# fpga-bank3-inside.net
KiCad netlist of a schematic drawn in Altium Designer
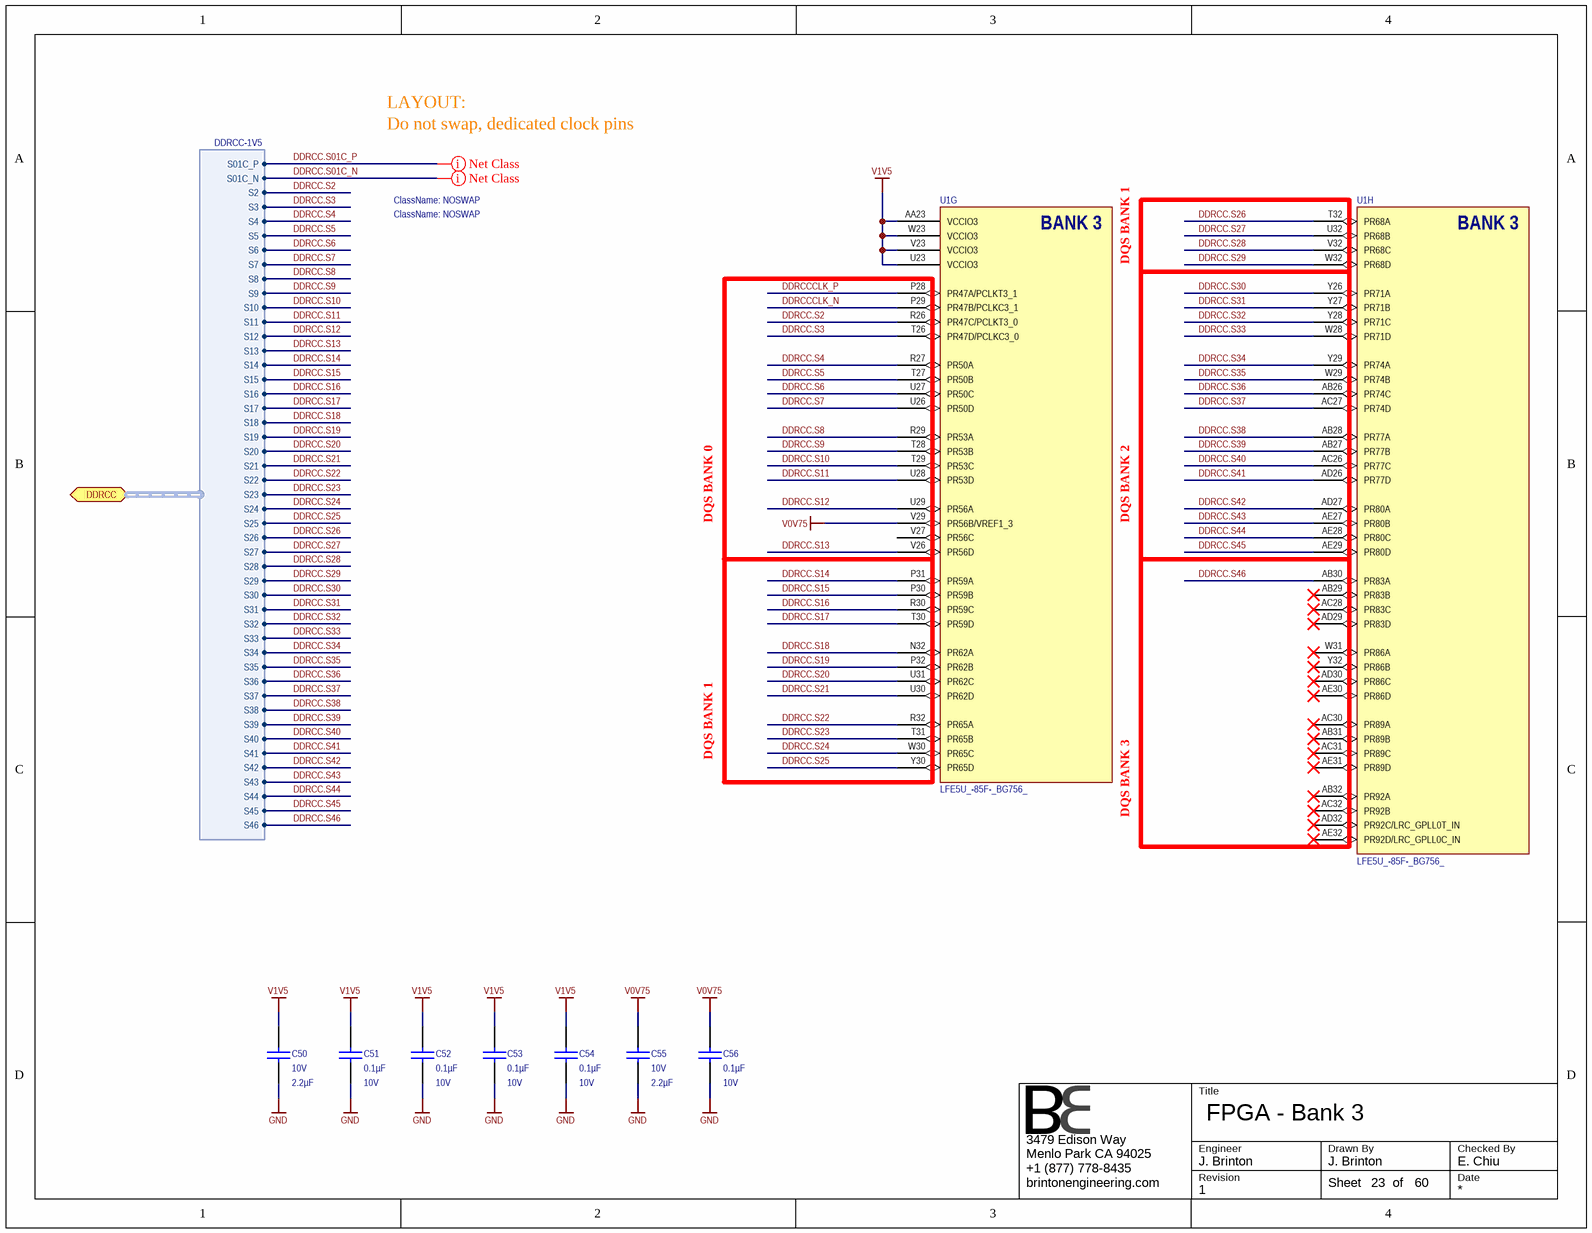
[diagram p0: fpga-bank3-inside.SchDoc]

(export (version "E")
  (design (tool "Eeschema 10.0.6"))
  (components
    (comp (ref "C50")
      (value "GRM188R71A225KE15D")
      (footprint "CAPC1608X90N")
      (description "CAP CER 2.2UF 10V 10% X7R 0603")
      (fields
        (field (name "MANUFACTURER") "Murata Electronics North America")
        (field (name "TOLERANCE") "±10%")
        (field (name "VOLTAGE - RATED") "10V")
        (field (name "CAPACITANCE") "2.2µF")
      )
      (libsource (lib "murata") (part "GRM188R71A225KE15D"))
    )
    (comp (ref "C51")
      (value "GRM155R71A104KA01J")
      (footprint "CAPC1005X56N")
      (description "CAP CER 0.1UF 10V 10% X7R 0402")
      (fields
        (field (name "MANUFACTURER") "Murata Electronics North America")
        (field (name "TOLERANCE") "±10%")
        (field (name "CAPACITANCE") "0.1µF")
        (field (name "VOLTAGE - RATED") "10V")
      )
      (libsource (lib "murata") (part "GRM155R71A104KA01J"))
    )
    (comp (ref "C52")
      (value "GRM155R71A104KA01J")
      (footprint "CAPC1005X56N")
      (description "CAP CER 0.1UF 10V 10% X7R 0402")
      (fields
        (field (name "MANUFACTURER") "Murata Electronics North America")
        (field (name "TOLERANCE") "±10%")
        (field (name "CAPACITANCE") "0.1µF")
        (field (name "VOLTAGE - RATED") "10V")
      )
      (libsource (lib "murata") (part "GRM155R71A104KA01J"))
    )
    (comp (ref "C53")
      (value "GRM155R71A104KA01J")
      (footprint "CAPC1005X56N")
      (description "CAP CER 0.1UF 10V 10% X7R 0402")
      (fields
        (field (name "MANUFACTURER") "Murata Electronics North America")
        (field (name "TOLERANCE") "±10%")
        (field (name "CAPACITANCE") "0.1µF")
        (field (name "VOLTAGE - RATED") "10V")
      )
      (libsource (lib "murata") (part "GRM155R71A104KA01J"))
    )
    (comp (ref "C54")
      (value "GRM155R71A104KA01J")
      (footprint "CAPC1005X56N")
      (description "CAP CER 0.1UF 10V 10% X7R 0402")
      (fields
        (field (name "MANUFACTURER") "Murata Electronics North America")
        (field (name "TOLERANCE") "±10%")
        (field (name "CAPACITANCE") "0.1µF")
        (field (name "VOLTAGE - RATED") "10V")
      )
      (libsource (lib "murata") (part "GRM155R71A104KA01J"))
    )
    (comp (ref "C55")
      (value "GRM188R71A225KE15D")
      (footprint "CAPC1608X90N")
      (description "CAP CER 2.2UF 10V 10% X7R 0603")
      (fields
        (field (name "MANUFACTURER") "Murata Electronics North America")
        (field (name "TOLERANCE") "±10%")
        (field (name "VOLTAGE - RATED") "10V")
        (field (name "CAPACITANCE") "2.2µF")
      )
      (libsource (lib "murata") (part "GRM188R71A225KE15D"))
    )
    (comp (ref "C56")
      (value "GRM155R71A104KA01J")
      (footprint "CAPC1005X56N")
      (description "CAP CER 0.1UF 10V 10% X7R 0402")
      (fields
        (field (name "MANUFACTURER") "Murata Electronics North America")
        (field (name "TOLERANCE") "±10%")
        (field (name "CAPACITANCE") "0.1µF")
        (field (name "VOLTAGE - RATED") "10V")
      )
      (libsource (lib "murata") (part "GRM155R71A104KA01J"))
    )
    (comp (ref "U1")
      (value "LFE5U_-85F-_BG756_")
      (footprint "lattice:caBGA756")
      (description "ECP5 FPGA, 85k LUT, 756-caBGA")
      (fields (field (name "MANUFACTURER") "Lattice Semiconductor"))
      (libsource (lib "lattice") (part "LFE5U_-85F-_BG756_"))
    )
  )
  (nets
    (net (code "4") (name "/DDRCC.S2") (class "Default")
      (node (ref "U1") (pin "R26") (pinfunction "PR47C/PCLKT3_0_R26") (pintype "bidirectional"))
    )
    (net (code "5") (name "/DDRCC.S3") (class "Default")
      (node (ref "U1") (pin "T26") (pinfunction "PR47D/PCLKC3_0_T26") (pintype "bidirectional"))
    )
    (net (code "6") (name "/DDRCC.S4") (class "Default")
      (node (ref "U1") (pin "R27") (pinfunction "PR50A_R27") (pintype "bidirectional"))
    )
    (net (code "7") (name "/DDRCC.S5") (class "Default")
      (node (ref "U1") (pin "T27") (pinfunction "PR50B_T27") (pintype "bidirectional"))
    )
    (net (code "8") (name "/DDRCC.S6") (class "Default")
      (node (ref "U1") (pin "U27") (pinfunction "PR50C_U27") (pintype "bidirectional"))
    )
    (net (code "9") (name "/DDRCC.S7") (class "Default")
      (node (ref "U1") (pin "U26") (pinfunction "PR50D_U26") (pintype "bidirectional"))
    )
    (net (code "10") (name "/DDRCC.S8") (class "Default")
      (node (ref "U1") (pin "R29") (pinfunction "PR53A_R29") (pintype "bidirectional"))
    )
    (net (code "11") (name "/DDRCC.S9") (class "Default")
      (node (ref "U1") (pin "T28") (pinfunction "PR53B_T28") (pintype "bidirectional"))
    )
    (net (code "12") (name "/DDRCC.S10") (class "Default")
      (node (ref "U1") (pin "T29") (pinfunction "PR53C_T29") (pintype "bidirectional"))
    )
    (net (code "13") (name "/DDRCC.S11") (class "Default")
      (node (ref "U1") (pin "U28") (pinfunction "PR53D_U28") (pintype "bidirectional"))
    )
    (net (code "14") (name "/DDRCC.S12") (class "Default")
      (node (ref "U1") (pin "U29") (pinfunction "PR56A_U29") (pintype "bidirectional"))
    )
    (net (code "15") (name "/DDRCC.S13") (class "Default")
      (node (ref "U1") (pin "V26") (pinfunction "PR56D_V26") (pintype "bidirectional"))
    )
    (net (code "16") (name "/DDRCC.S14") (class "Default")
      (node (ref "U1") (pin "P31") (pinfunction "PR59A_P31") (pintype "bidirectional"))
    )
    (net (code "17") (name "/DDRCC.S15") (class "Default")
      (node (ref "U1") (pin "P30") (pinfunction "PR59B_P30") (pintype "bidirectional"))
    )
    (net (code "18") (name "/DDRCC.S16") (class "Default")
      (node (ref "U1") (pin "R30") (pinfunction "PR59C_R30") (pintype "bidirectional"))
    )
    (net (code "19") (name "/DDRCC.S17") (class "Default")
      (node (ref "U1") (pin "T30") (pinfunction "PR59D_T30") (pintype "bidirectional"))
    )
    (net (code "20") (name "/DDRCC.S18") (class "Default")
      (node (ref "U1") (pin "N32") (pinfunction "PR62A_N32") (pintype "bidirectional"))
    )
    (net (code "21") (name "/DDRCC.S19") (class "Default")
      (node (ref "U1") (pin "P32") (pinfunction "PR62B_P32") (pintype "bidirectional"))
    )
    (net (code "22") (name "/DDRCC.S20") (class "Default")
      (node (ref "U1") (pin "U31") (pinfunction "PR62C_U31") (pintype "bidirectional"))
    )
    (net (code "23") (name "/DDRCC.S21") (class "Default")
      (node (ref "U1") (pin "U30") (pinfunction "PR62D_U30") (pintype "bidirectional"))
    )
    (net (code "24") (name "/DDRCC.S22") (class "Default")
      (node (ref "U1") (pin "R32") (pinfunction "PR65A_R32") (pintype "bidirectional"))
    )
    (net (code "25") (name "/DDRCC.S23") (class "Default")
      (node (ref "U1") (pin "T31") (pinfunction "PR65B_T31") (pintype "bidirectional"))
    )
    (net (code "26") (name "/DDRCC.S24") (class "Default")
      (node (ref "U1") (pin "W30") (pinfunction "PR65C_W30") (pintype "bidirectional"))
    )
    (net (code "27") (name "/DDRCC.S25") (class "Default")
      (node (ref "U1") (pin "Y30") (pinfunction "PR65D_Y30") (pintype "bidirectional"))
    )
    (net (code "28") (name "/DDRCC.S26") (class "Default")
      (node (ref "U1") (pin "T32") (pinfunction "PR68A_T32") (pintype "bidirectional"))
    )
    (net (code "29") (name "/DDRCC.S27") (class "Default")
      (node (ref "U1") (pin "U32") (pinfunction "PR68B_U32") (pintype "bidirectional"))
    )
    (net (code "30") (name "/DDRCC.S28") (class "Default")
      (node (ref "U1") (pin "V32") (pinfunction "PR68C_V32") (pintype "bidirectional"))
    )
    (net (code "31") (name "/DDRCC.S29") (class "Default")
      (node (ref "U1") (pin "W32") (pinfunction "PR68D_W32") (pintype "bidirectional"))
    )
    (net (code "32") (name "/DDRCC.S30") (class "Default")
      (node (ref "U1") (pin "Y26") (pinfunction "PR71A_Y26") (pintype "bidirectional"))
    )
    (net (code "33") (name "/DDRCC.S31") (class "Default")
      (node (ref "U1") (pin "Y27") (pinfunction "PR71B_Y27") (pintype "bidirectional"))
    )
    (net (code "34") (name "/DDRCC.S32") (class "Default")
      (node (ref "U1") (pin "Y28") (pinfunction "PR71C_Y28") (pintype "bidirectional"))
    )
    (net (code "35") (name "/DDRCC.S33") (class "Default")
      (node (ref "U1") (pin "W28") (pinfunction "PR71D_W28") (pintype "bidirectional"))
    )
    (net (code "36") (name "/DDRCC.S34") (class "Default")
      (node (ref "U1") (pin "Y29") (pinfunction "PR74A_Y29") (pintype "bidirectional"))
    )
    (net (code "37") (name "/DDRCC.S35") (class "Default")
      (node (ref "U1") (pin "W29") (pinfunction "PR74B_W29") (pintype "bidirectional"))
    )
    (net (code "38") (name "/DDRCC.S36") (class "Default")
      (node (ref "U1") (pin "AB26") (pinfunction "PR74C_AB26") (pintype "bidirectional"))
    )
    (net (code "39") (name "/DDRCC.S37") (class "Default")
      (node (ref "U1") (pin "AC27") (pinfunction "PR74D_AC27") (pintype "bidirectional"))
    )
    (net (code "40") (name "/DDRCC.S38") (class "Default")
      (node (ref "U1") (pin "AB28") (pinfunction "PR77A_AB28") (pintype "bidirectional"))
    )
    (net (code "41") (name "/DDRCC.S39") (class "Default")
      (node (ref "U1") (pin "AB27") (pinfunction "PR77B_AB27") (pintype "bidirectional"))
    )
    (net (code "42") (name "/DDRCC.S40") (class "Default")
      (node (ref "U1") (pin "AC26") (pinfunction "PR77C_AC26") (pintype "bidirectional"))
    )
    (net (code "43") (name "/DDRCC.S41") (class "Default")
      (node (ref "U1") (pin "AD26") (pinfunction "PR77D_AD26") (pintype "bidirectional"))
    )
    (net (code "44") (name "/DDRCC.S42") (class "Default")
      (node (ref "U1") (pin "AD27") (pinfunction "PR80A_AD27") (pintype "bidirectional"))
    )
    (net (code "45") (name "/DDRCC.S43") (class "Default")
      (node (ref "U1") (pin "AE27") (pinfunction "PR80B_AE27") (pintype "bidirectional"))
    )
    (net (code "46") (name "/DDRCC.S44") (class "Default")
      (node (ref "U1") (pin "AE28") (pinfunction "PR80C_AE28") (pintype "bidirectional"))
    )
    (net (code "47") (name "/DDRCC.S45") (class "Default")
      (node (ref "U1") (pin "AE29") (pinfunction "PR80D_AE29") (pintype "bidirectional"))
    )
    (net (code "48") (name "/DDRCC.S46") (class "Default")
      (node (ref "U1") (pin "AB30") (pinfunction "PR83A_AB30") (pintype "bidirectional"))
    )
    (net (code "49") (name "/DDRCCCLK_N") (class "Default")
      (node (ref "U1") (pin "P29") (pinfunction "PR47B/PCLKC3_1_P29") (pintype "bidirectional"))
    )
    (net (code "50") (name "/DDRCCCLK_P") (class "Default")
      (node (ref "U1") (pin "P28") (pinfunction "PR47A/PCLKT3_1_P28") (pintype "bidirectional"))
    )
    (net (code "52") (name "GND") (class "Default")
      (node (ref "C50") (pin "1") (pinfunction "1_1") (pintype "passive"))
      (node (ref "C51") (pin "1") (pinfunction "1_1") (pintype "passive"))
      (node (ref "C52") (pin "1") (pinfunction "1_1") (pintype "passive"))
      (node (ref "C53") (pin "1") (pinfunction "1_1") (pintype "passive"))
      (node (ref "C54") (pin "1") (pinfunction "1_1") (pintype "passive"))
      (node (ref "C55") (pin "1") (pinfunction "1_1") (pintype "passive"))
      (node (ref "C56") (pin "1") (pinfunction "1_1") (pintype "passive"))
    )
    (net (code "53") (name "V0V75") (class "Default")
      (node (ref "C55") (pin "2") (pinfunction "2_2") (pintype "passive"))
      (node (ref "C56") (pin "2") (pinfunction "2_2") (pintype "passive"))
      (node (ref "U1") (pin "V29") (pinfunction "PR56B/VREF1_3_V29") (pintype "bidirectional"))
    )
    (net (code "54") (name "V1V5") (class "Default")
      (node (ref "C50") (pin "2") (pinfunction "2_2") (pintype "passive"))
      (node (ref "C51") (pin "2") (pinfunction "2_2") (pintype "passive"))
      (node (ref "C52") (pin "2") (pinfunction "2_2") (pintype "passive"))
      (node (ref "C53") (pin "2") (pinfunction "2_2") (pintype "passive"))
      (node (ref "C54") (pin "2") (pinfunction "2_2") (pintype "passive"))
      (node (ref "U1") (pin "AA23") (pinfunction "VCCIO3_AA23") (pintype "power_in"))
      (node (ref "U1") (pin "U23") (pinfunction "VCCIO3_U23") (pintype "power_in"))
      (node (ref "U1") (pin "V23") (pinfunction "VCCIO3_V23") (pintype "power_in"))
      (node (ref "U1") (pin "W23") (pinfunction "VCCIO3_W23") (pintype "power_in"))
    )
    (net (code "55") (name "unconnected-(U1G-PR56C-PadV27)") (class "Default")
      (node (ref "U1") (pin "V27") (pinfunction "PR56C_V27") (pintype "bidirectional"))
    )
    (net (code "56") (name "unconnected-(U1H-PR83B-PadAB29)") (class "Default")
      (node (ref "U1") (pin "AB29") (pinfunction "PR83B_AB29") (pintype "bidirectional+no_connect"))
    )
    (net (code "57") (name "unconnected-(U1H-PR83C-PadAC28)") (class "Default")
      (node (ref "U1") (pin "AC28") (pinfunction "PR83C_AC28") (pintype "bidirectional+no_connect"))
    )
    (net (code "58") (name "unconnected-(U1H-PR83D-PadAD29)") (class "Default")
      (node (ref "U1") (pin "AD29") (pinfunction "PR83D_AD29") (pintype "bidirectional+no_connect"))
    )
    (net (code "59") (name "unconnected-(U1H-PR86A-PadW31)") (class "Default")
      (node (ref "U1") (pin "W31") (pinfunction "PR86A_W31") (pintype "bidirectional+no_connect"))
    )
    (net (code "60") (name "unconnected-(U1H-PR86B-PadY32)") (class "Default")
      (node (ref "U1") (pin "Y32") (pinfunction "PR86B_Y32") (pintype "bidirectional+no_connect"))
    )
    (net (code "61") (name "unconnected-(U1H-PR86C-PadAD30)") (class "Default")
      (node (ref "U1") (pin "AD30") (pinfunction "PR86C_AD30") (pintype "bidirectional+no_connect"))
    )
    (net (code "62") (name "unconnected-(U1H-PR86D-PadAE30)") (class "Default")
      (node (ref "U1") (pin "AE30") (pinfunction "PR86D_AE30") (pintype "bidirectional+no_connect"))
    )
    (net (code "63") (name "unconnected-(U1H-PR89A-PadAC30)") (class "Default")
      (node (ref "U1") (pin "AC30") (pinfunction "PR89A_AC30") (pintype "bidirectional+no_connect"))
    )
    (net (code "64") (name "unconnected-(U1H-PR89B-PadAB31)") (class "Default")
      (node (ref "U1") (pin "AB31") (pinfunction "PR89B_AB31") (pintype "bidirectional+no_connect"))
    )
    (net (code "65") (name "unconnected-(U1H-PR89C-PadAC31)") (class "Default")
      (node (ref "U1") (pin "AC31") (pinfunction "PR89C_AC31") (pintype "bidirectional+no_connect"))
    )
    (net (code "66") (name "unconnected-(U1H-PR89D-PadAE31)") (class "Default")
      (node (ref "U1") (pin "AE31") (pinfunction "PR89D_AE31") (pintype "bidirectional+no_connect"))
    )
    (net (code "67") (name "unconnected-(U1H-PR92A-PadAB32)") (class "Default")
      (node (ref "U1") (pin "AB32") (pinfunction "PR92A_AB32") (pintype "bidirectional+no_connect"))
    )
    (net (code "68") (name "unconnected-(U1H-PR92B-PadAC32)") (class "Default")
      (node (ref "U1") (pin "AC32") (pinfunction "PR92B_AC32") (pintype "bidirectional+no_connect"))
    )
    (net (code "69") (name "unconnected-(U1H-PR92C{slash}LRC_GPLL0T_IN-PadAD32)") (class "Default")
      (node (ref "U1") (pin "AD32") (pinfunction "PR92C/LRC_GPLL0T_IN_AD32") (pintype "bidirectional+no_connect"))
    )
    (net (code "70") (name "unconnected-(U1H-PR92D{slash}LRC_GPLL0C_IN-PadAE32)") (class "Default")
      (node (ref "U1") (pin "AE32") (pinfunction "PR92D/LRC_GPLL0C_IN_AE32") (pintype "bidirectional+no_connect"))
    )
  )
)
